# etna-main-usb.net
KiCad netlist of a schematic drawn in Altium Designer
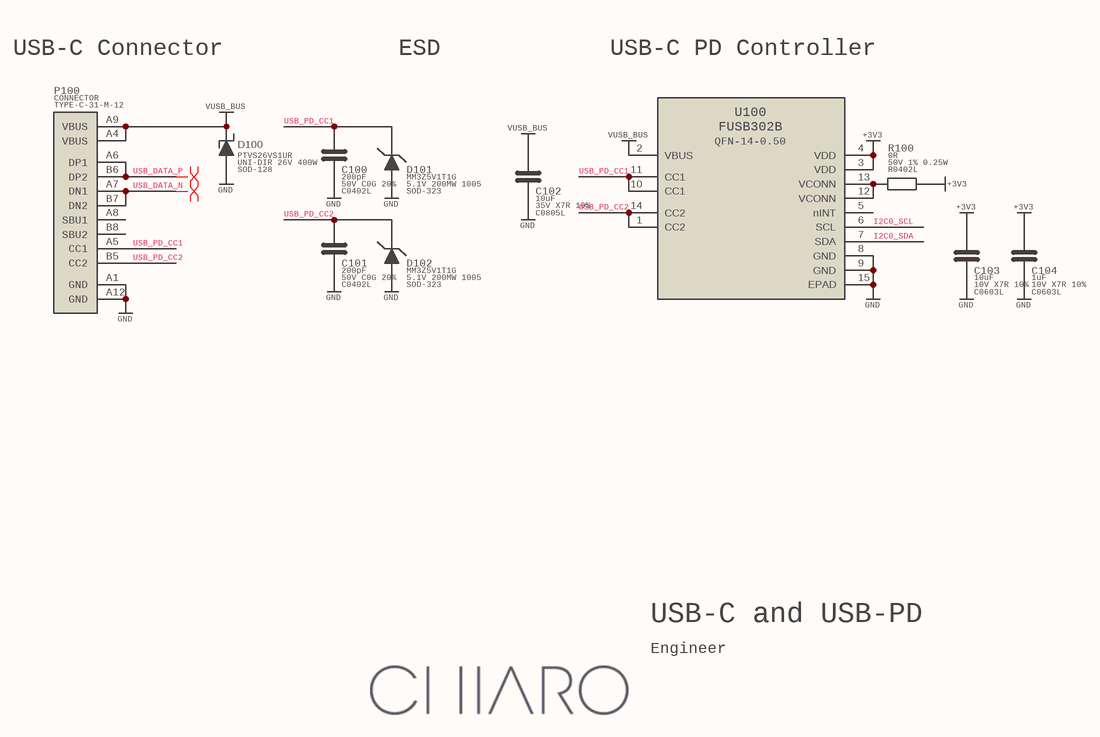
[diagram p0: etna-main-usb.SchDoc]

(export (version "E")
  (design (tool "Eeschema 10.0.6"))
  (components
    (comp (ref "C100")
      (value "200pF")
      (footprint "C0402L")
      (fields (field (name "SPECIFICATION") "50V C0G 20%"))
      (libsource (lib "passive") (part "CAPACITOR_NONPOL"))
    )
    (comp (ref "C101")
      (value "200pF")
      (footprint "C0402L")
      (fields (field (name "SPECIFICATION") "50V C0G 20%"))
      (libsource (lib "passive") (part "CAPACITOR_NONPOL"))
    )
    (comp (ref "C102")
      (value "10uF")
      (footprint "C0805L")
      (fields (field (name "SPECIFICATION") "35V X7R 10%") (field (name "Comment") "100n"))
      (libsource (lib "discreet") (part "CAPACITOR_NONPOL"))
    )
    (comp (ref "C103")
      (value "10uF")
      (footprint "C0603L")
      (fields (field (name "SPECIFICATION") "10V X7R 10%") (field (name "Comment") "100n"))
      (libsource (lib "discreet") (part "CAPACITOR_NONPOL"))
    )
    (comp (ref "C104")
      (value "1uF")
      (footprint "C0603L")
      (fields (field (name "SPECIFICATION") "10V X7R 10%") (field (name "Comment") "100n"))
      (libsource (lib "discreet") (part "CAPACITOR_NONPOL"))
    )
    (comp (ref "D100")
      (value "PTVS26VS1UR")
      (footprint "SOD-128")
      (fields (field (name "SPECIFICATION") "UNI-DIR 26V 400W") (field (name "Comment") "DIODE_ZEN"))
      (libsource (lib "discreet") (part "DIODE_ZEN"))
    )
    (comp (ref "D101")
      (value "MM3Z5V1T1G")
      (footprint "SOD-323")
      (fields (field (name "SPECIFICATION") "5.1V 200MW 1005") (field (name "Comment") "DIODE_TVS"))
      (libsource (lib "discreet") (part "DIODE_TVS"))
    )
    (comp (ref "D102")
      (value "MM3Z5V1T1G")
      (footprint "SOD-323")
      (fields (field (name "SPECIFICATION") "5.1V 200MW 1005") (field (name "Comment") "DIODE_TVS"))
      (libsource (lib "discreet") (part "DIODE_TVS"))
    )
    (comp (ref "P100")
      (value "CONNECTOR")
      (footprint "TYPE-C-31-M-12")
      (description "TYPE-C-31-M-12")
      (libsource (lib "connectors") (part "TYPE-C-31-M-12"))
    )
    (comp (ref "R100")
      (value "0R")
      (footprint "R0402L")
      (fields (field (name "SPECIFICATION") "50V 1% 0.25W"))
      (libsource (lib "passive") (part "RESISTOR"))
    )
    (comp (ref "U100") (value "FUSB302B") (footprint "QFN-14-0.50") (libsource (lib "ic") (part "FUSB302B")))
  )
  (nets
    (net (code "1") (name "+3V3") (class "Default")
      (node (ref "C103") (pin "1") (pinfunction "1_1") (pintype "passive"))
      (node (ref "C104") (pin "1") (pinfunction "1_1") (pintype "passive"))
      (node (ref "R100") (pin "1") (pinfunction "1_1") (pintype "passive"))
      (node (ref "U100") (pin "3") (pinfunction "VDD_3") (pintype "passive"))
      (node (ref "U100") (pin "4") (pinfunction "VDD_4") (pintype "passive"))
    )
    (net (code "2") (name "/I2C0_SCL") (class "Default")
      (node (ref "U100") (pin "6") (pinfunction "SCL_6") (pintype "passive"))
    )
    (net (code "3") (name "/I2C0_SDA") (class "Default")
      (node (ref "U100") (pin "7") (pinfunction "SDA_7") (pintype "passive"))
    )
    (net (code "4") (name "/USB_DATA_N") (class "Default")
      (node (ref "P100") (pin "A7") (pinfunction "DN1_A7") (pintype "passive"))
      (node (ref "P100") (pin "B7") (pinfunction "DN2_B7") (pintype "passive"))
    )
    (net (code "5") (name "/USB_DATA_P") (class "Default")
      (node (ref "P100") (pin "A6") (pinfunction "DP1_A6") (pintype "passive"))
      (node (ref "P100") (pin "B6") (pinfunction "DP2_B6") (pintype "passive"))
    )
    (net (code "6") (name "/USB_PD_CC1") (class "Default")
      (node (ref "C100") (pin "1") (pinfunction "1_1") (pintype "passive"))
      (node (ref "D101") (pin "2") (pinfunction "K_2") (pintype "passive"))
      (node (ref "P100") (pin "A5") (pinfunction "CC1_A5") (pintype "passive"))
      (node (ref "U100") (pin "10") (pinfunction "CC1_10") (pintype "passive"))
      (node (ref "U100") (pin "11") (pinfunction "CC1_11") (pintype "passive"))
    )
    (net (code "7") (name "/USB_PD_CC2") (class "Default")
      (node (ref "C101") (pin "1") (pinfunction "1_1") (pintype "passive"))
      (node (ref "D102") (pin "2") (pinfunction "K_2") (pintype "passive"))
      (node (ref "P100") (pin "B5") (pinfunction "CC2_B5") (pintype "passive"))
      (node (ref "U100") (pin "1") (pinfunction "CC2_1") (pintype "passive"))
      (node (ref "U100") (pin "14") (pinfunction "CC2_14") (pintype "passive"))
    )
    (net (code "8") (name "GND") (class "Default")
      (node (ref "C100") (pin "2") (pinfunction "2_2") (pintype "passive"))
      (node (ref "C101") (pin "2") (pinfunction "2_2") (pintype "passive"))
      (node (ref "C102") (pin "2") (pinfunction "2_2") (pintype "passive"))
      (node (ref "C103") (pin "2") (pinfunction "2_2") (pintype "passive"))
      (node (ref "C104") (pin "2") (pinfunction "2_2") (pintype "passive"))
      (node (ref "D100") (pin "1") (pinfunction "A_1") (pintype "passive"))
      (node (ref "D101") (pin "1") (pinfunction "A_1") (pintype "passive"))
      (node (ref "D102") (pin "1") (pinfunction "A_1") (pintype "passive"))
      (node (ref "P100") (pin "A1") (pinfunction "GND_A1") (pintype "passive"))
      (node (ref "P100") (pin "A12") (pinfunction "GND_A12") (pintype "passive"))
      (node (ref "U100") (pin "15") (pinfunction "EPAD_15") (pintype "passive"))
      (node (ref "U100") (pin "8") (pinfunction "GND_8") (pintype "passive"))
      (node (ref "U100") (pin "9") (pinfunction "GND_9") (pintype "passive"))
    )
    (net (code "9") (name "Net-(R100-Pad2)") (class "Default")
      (node (ref "R100") (pin "2") (pinfunction "2_2") (pintype "passive"))
      (node (ref "U100") (pin "12") (pinfunction "VCONN_12") (pintype "passive"))
      (node (ref "U100") (pin "13") (pinfunction "VCONN_13") (pintype "passive"))
    )
    (net (code "10") (name "VUSB_BUS") (class "Default")
      (node (ref "C102") (pin "1") (pinfunction "1_1") (pintype "passive"))
      (node (ref "D100") (pin "2") (pinfunction "K_2") (pintype "passive"))
      (node (ref "P100") (pin "A4") (pinfunction "VBUS_A4") (pintype "passive"))
      (node (ref "P100") (pin "A9") (pinfunction "VBUS_A9") (pintype "passive"))
      (node (ref "U100") (pin "2") (pinfunction "VBUS_2") (pintype "passive"))
    )
    (net (code "11") (name "unconnected-(P100-SBU1-PadA8)") (class "Default")
      (node (ref "P100") (pin "A8") (pinfunction "SBU1_A8") (pintype "passive"))
    )
    (net (code "12") (name "unconnected-(P100-SBU2-PadB8)") (class "Default")
      (node (ref "P100") (pin "B8") (pinfunction "SBU2_B8") (pintype "passive"))
    )
    (net (code "13") (name "unconnected-(U100-N.C.-Pad44)") (class "Default")
      (node (ref "U100") (pin "44") (pinfunction "N.C._44") (pintype "passive"))
    )
    (net (code "14") (name "unconnected-(U100-nINT-Pad5)") (class "Default")
      (node (ref "U100") (pin "5") (pinfunction "nINT_5") (pintype "passive"))
    )
  )
)
